# MCU.net
KiCad netlist of a schematic drawn in Altium Designer
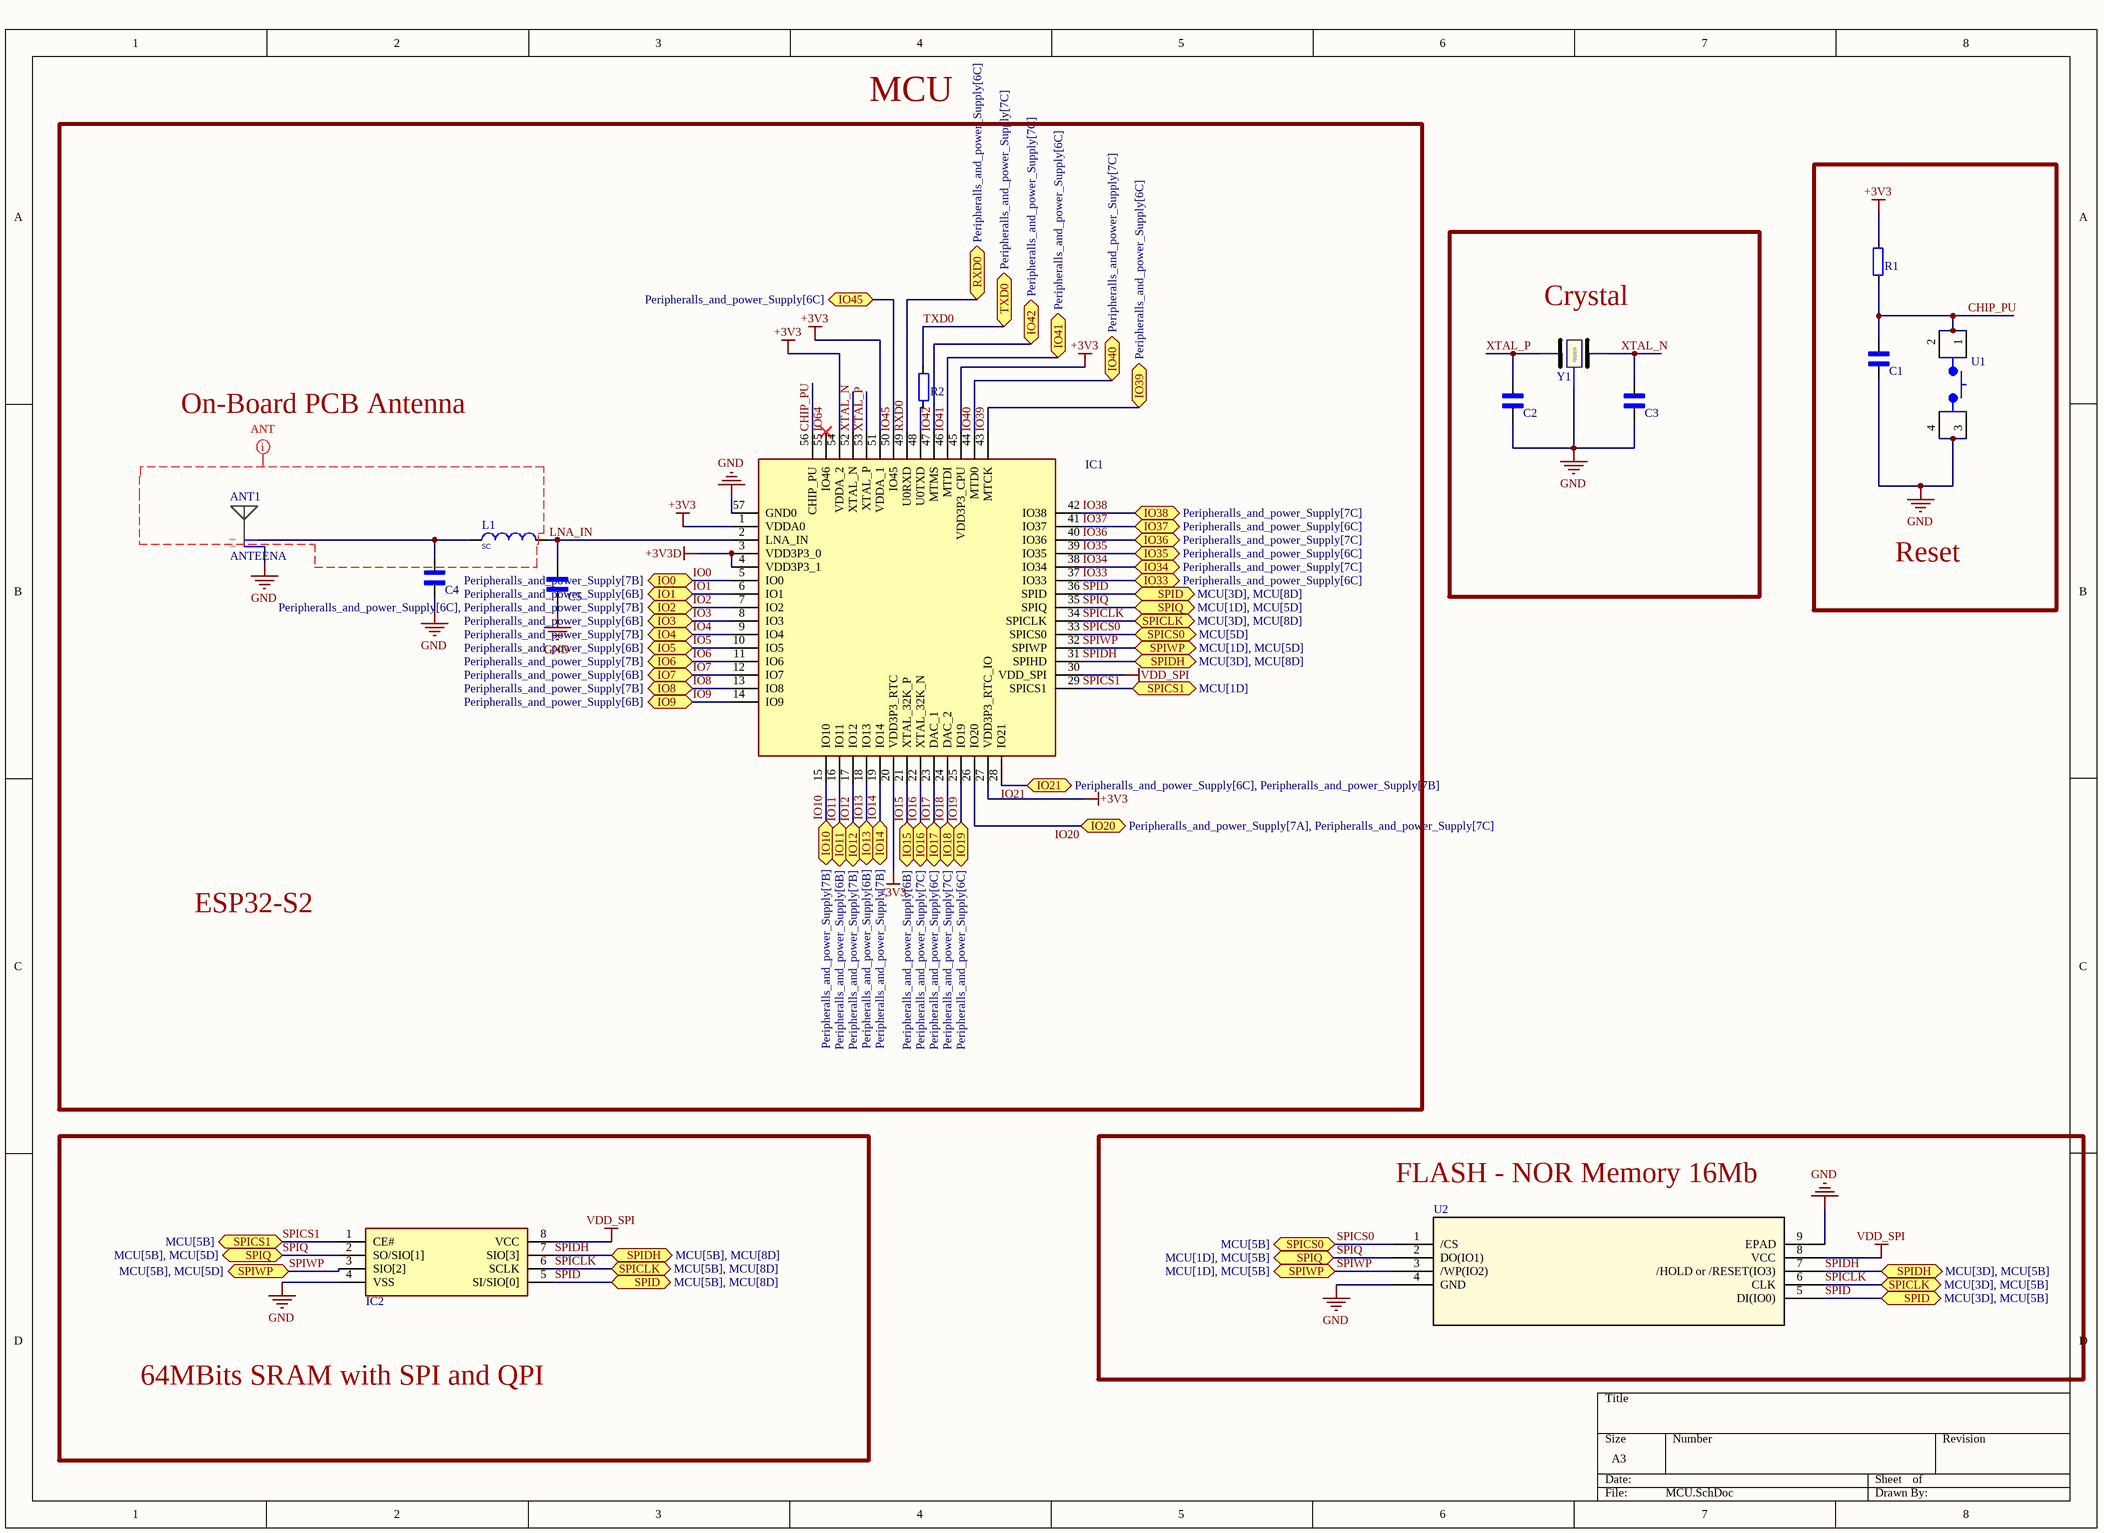
[diagram p0: MCU.SchDoc]

(export (version "E")
  (design (tool "Eeschema 10.0.6"))
  (components
    (comp (ref "ANT1")
      (value "ANTEENA")
      (footprint "Antenna_2.4GHz")
      (libsource (lib "ESP32-S2") (part "ANTEENA"))
    )
    (comp (ref "C1") (value "CAP_0603") (footprint "CAP_0603") (libsource (lib "") (part "CAP_0603_1")))
    (comp (ref "C2") (value "CAP_0603") (footprint "CAP_0603") (libsource (lib "ESP32-S2") (part "CAP_0603")))
    (comp (ref "C3") (value "CAP_0603") (footprint "CAP_0603") (libsource (lib "ESP32-S2") (part "CAP_0603")))
    (comp (ref "C4") (value "CAP_0603") (footprint "CAP_0603") (libsource (lib "ESP32-S2") (part "CAP_0603")))
    (comp (ref "C5") (value "CAP_0603") (footprint "CAP_0603") (libsource (lib "ESP32-S2") (part "CAP_0603")))
    (comp (ref "IC1")
      (value "ESP32-S2")
      (footprint "QFN-56")
      (description "SMD WI-FI IC, ESP32-S2, SINGAL-C")
      (fields (field (name "MF") "Espressif Systems"))
      (libsource (lib "ESP32-S2") (part "ESP32-S2"))
    )
    (comp (ref "IC2")
      (value "PSRAM")
      (footprint "SOIC8 _PSRAM")
      (description "SOP-8_150mil  SRAM ROHS")
      (fields (field (name "MANUFACTURER_PART_NUMBER") "LY68L6400SLIT"))
      (libsource (lib "ESP32-S2") (part "LY68L6400SLIT"))
    )
    (comp (ref "L1")
      (value "SC")
      (footprint "IND_0402")
      (description "Inductor RF Chip Multi-Layer 2nH 0.3nH 100MHz 8Q-Factor Air 900mA 90mOhm DCR 0402 Automotive T/R")
      (fields (field (name "MP") "LQG15HZ2N0S02D") (field (name "Comment") "IND_0402"))
      (libsource (lib "ESP32-S2") (part "IND_2.0nH_0402"))
    )
    (comp (ref "R1") (value "RES_0603") (footprint "RES_0603") (libsource (lib "ESP32-S2") (part "RES_0603")))
    (comp (ref "R2") (value "RES_0603") (footprint "RES_0603") (libsource (lib "ESP32-S2") (part "RES_0603")))
    (comp (ref "U1")
      (value "TACT SWITCH")
      (footprint "SW_TL3305AF260QG")
      (description "Tactile Switch SPST-NO Top Actuated Surface Mount")
      (fields (field (name "MF") "E-Switch") (field (name "MP") "TL3305AF260QG"))
      (libsource (lib "ESP32-S2") (part "TL3305AF260QG"))
    )
    (comp (ref "U2")
      (value "NOR FLASH IC")
      (footprint "FLASH USON2x3x0.6mm")
      (description "FLASH - NOR Memory IC 16Mb (2M x 8) SPI - Quad I/O 133 MHz 6 ns 8-USON (2x3)")
      (fields
        (field (name "MANUFACTURER_PART_NUMBER") "W25Q16JVUXIQ")
        (field (name "COPYRIGHT") "Copyright (C) 2022 Ultra Librarian. All rights reserved.")
      )
      (libsource (lib "ESP32-S2") (part "W25Q16JVUXIQ"))
    )
    (comp (ref "Y1")
      (value "CRYSTAL")
      (footprint "3225_CRYSTA_4P")
      (description "CRYSTAL_40MhZ_10ppm_15pF")
      (libsource (lib "ESP32-S2") (part "CRYSTAL_40MhZ_10ppm_15pF"))
    )
  )
  (nets
    (net (code "1") (name "+3V3") (class "Default")
      (node (ref "IC1") (pin "1") (pinfunction "VDDA0_1") (pintype "passive"))
      (node (ref "IC1") (pin "20") (pinfunction "VDD3P3_RTC_20") (pintype "passive"))
      (node (ref "IC1") (pin "27") (pinfunction "VDD3P3_RTC_IO_27") (pintype "passive"))
      (node (ref "IC1") (pin "45") (pinfunction "VDD3P3_CPU_45") (pintype "passive"))
      (node (ref "IC1") (pin "51") (pinfunction "VDDA_1_51") (pintype "passive"))
      (node (ref "IC1") (pin "54") (pinfunction "VDDA_2_54") (pintype "passive"))
      (node (ref "R1") (pin "1") (pinfunction "1_1") (pintype "passive"))
    )
    (net (code "2") (name "+3V3D") (class "Default")
      (node (ref "IC1") (pin "3") (pinfunction "VDD3P3_0_3") (pintype "passive"))
      (node (ref "IC1") (pin "4") (pinfunction "VDD3P3_1_4") (pintype "passive"))
    )
    (net (code "3") (name "/CHIP_PU") (class "Default")
      (node (ref "C1") (pin "1") (pinfunction "1_1") (pintype "passive"))
      (node (ref "IC1") (pin "56") (pinfunction "CHIP_PU_56") (pintype "passive"))
      (node (ref "R1") (pin "2") (pinfunction "2_2") (pintype "passive"))
      (node (ref "U1") (pin "1") (pinfunction "1_1") (pintype "passive"))
      (node (ref "U1") (pin "2") (pinfunction "2_2") (pintype "passive"))
    )
    (net (code "4") (name "/IO0") (class "Default")
      (node (ref "IC1") (pin "5") (pinfunction "IO0_5") (pintype "passive"))
    )
    (net (code "5") (name "/IO1") (class "Default")
      (node (ref "IC1") (pin "6") (pinfunction "IO1_6") (pintype "passive"))
    )
    (net (code "6") (name "/IO2") (class "Default")
      (node (ref "IC1") (pin "7") (pinfunction "IO2_7") (pintype "passive"))
    )
    (net (code "7") (name "/IO3") (class "Default")
      (node (ref "IC1") (pin "8") (pinfunction "IO3_8") (pintype "passive"))
    )
    (net (code "8") (name "/IO4") (class "Default")
      (node (ref "IC1") (pin "9") (pinfunction "IO4_9") (pintype "passive"))
    )
    (net (code "9") (name "/IO5") (class "Default")
      (node (ref "IC1") (pin "10") (pinfunction "IO5_10") (pintype "passive"))
    )
    (net (code "10") (name "/IO6") (class "Default")
      (node (ref "IC1") (pin "11") (pinfunction "IO6_11") (pintype "passive"))
    )
    (net (code "11") (name "/IO7") (class "Default")
      (node (ref "IC1") (pin "12") (pinfunction "IO7_12") (pintype "passive"))
    )
    (net (code "12") (name "/IO8") (class "Default")
      (node (ref "IC1") (pin "13") (pinfunction "IO8_13") (pintype "passive"))
    )
    (net (code "13") (name "/IO9") (class "Default")
      (node (ref "IC1") (pin "14") (pinfunction "IO9_14") (pintype "passive"))
    )
    (net (code "14") (name "/IO10") (class "Default")
      (node (ref "IC1") (pin "15") (pinfunction "IO10_15") (pintype "passive"))
    )
    (net (code "15") (name "/IO11") (class "Default")
      (node (ref "IC1") (pin "16") (pinfunction "IO11_16") (pintype "passive"))
    )
    (net (code "16") (name "/IO12") (class "Default")
      (node (ref "IC1") (pin "17") (pinfunction "IO12_17") (pintype "passive"))
    )
    (net (code "17") (name "/IO13") (class "Default")
      (node (ref "IC1") (pin "18") (pinfunction "IO13_18") (pintype "passive"))
    )
    (net (code "18") (name "/IO14") (class "Default")
      (node (ref "IC1") (pin "19") (pinfunction "IO14_19") (pintype "passive"))
    )
    (net (code "19") (name "/IO15") (class "Default")
      (node (ref "IC1") (pin "21") (pinfunction "XTAL_32K_P_21") (pintype "passive"))
    )
    (net (code "20") (name "/IO16") (class "Default")
      (node (ref "IC1") (pin "22") (pinfunction "XTAL_32K_N_22") (pintype "passive"))
    )
    (net (code "21") (name "/IO17") (class "Default")
      (node (ref "IC1") (pin "23") (pinfunction "DAC_1_23") (pintype "passive"))
    )
    (net (code "22") (name "/IO18") (class "Default")
      (node (ref "IC1") (pin "24") (pinfunction "DAC_2_24") (pintype "passive"))
    )
    (net (code "23") (name "/IO19") (class "Default")
      (node (ref "IC1") (pin "25") (pinfunction "IO19_25") (pintype "passive"))
    )
    (net (code "24") (name "/IO20") (class "Default")
      (node (ref "IC1") (pin "26") (pinfunction "IO20_26") (pintype "passive"))
    )
    (net (code "25") (name "/IO21") (class "Default")
      (node (ref "IC1") (pin "28") (pinfunction "IO21_28") (pintype "passive"))
    )
    (net (code "26") (name "/IO33") (class "Default")
      (node (ref "IC1") (pin "37") (pinfunction "IO33_37") (pintype "passive"))
    )
    (net (code "27") (name "/IO34") (class "Default")
      (node (ref "IC1") (pin "38") (pinfunction "IO34_38") (pintype "passive"))
    )
    (net (code "28") (name "/IO35") (class "Default")
      (node (ref "IC1") (pin "39") (pinfunction "IO35_39") (pintype "passive"))
    )
    (net (code "29") (name "/IO36") (class "Default")
      (node (ref "IC1") (pin "40") (pinfunction "IO36_40") (pintype "passive"))
    )
    (net (code "30") (name "/IO37") (class "Default")
      (node (ref "IC1") (pin "41") (pinfunction "IO37_41") (pintype "passive"))
    )
    (net (code "31") (name "/IO38") (class "Default")
      (node (ref "IC1") (pin "42") (pinfunction "IO38_42") (pintype "passive"))
    )
    (net (code "32") (name "/IO39") (class "Default")
      (node (ref "IC1") (pin "43") (pinfunction "MTCK_43") (pintype "passive"))
    )
    (net (code "33") (name "/IO40") (class "Default")
      (node (ref "IC1") (pin "44") (pinfunction "MTD0_44") (pintype "passive"))
    )
    (net (code "34") (name "/IO41") (class "Default")
      (node (ref "IC1") (pin "46") (pinfunction "MTDI_46") (pintype "passive"))
    )
    (net (code "35") (name "/IO42") (class "Default")
      (node (ref "IC1") (pin "47") (pinfunction "MTMS_47") (pintype "passive"))
    )
    (net (code "36") (name "/IO45") (class "Default")
      (node (ref "IC1") (pin "50") (pinfunction "IO45_50") (pintype "passive"))
    )
    (net (code "37") (name "/IO64") (class "Default")
      (node (ref "IC1") (pin "55") (pinfunction "IO46_55") (pintype "passive+no_connect"))
    )
    (net (code "38") (name "/LNA_IN") (class "Default")
      (node (ref "C5") (pin "2") (pinfunction "2_2") (pintype "passive"))
      (node (ref "IC1") (pin "2") (pinfunction "LNA_IN_2") (pintype "passive"))
      (node (ref "L1") (pin "2") (pinfunction "2_2") (pintype "passive"))
    )
    (net (code "39") (name "/RXD0") (class "Default")
      (node (ref "IC1") (pin "49") (pinfunction "U0RXD_49") (pintype "passive"))
    )
    (net (code "40") (name "/SPICLK") (class "Default")
      (node (ref "IC1") (pin "34") (pinfunction "SPICLK_34") (pintype "passive"))
      (node (ref "IC2") (pin "6") (pinfunction "SCLK_6") (pintype "passive"))
      (node (ref "U2") (pin "6") (pinfunction "CLK_6") (pintype "passive"))
    )
    (net (code "41") (name "/SPICS0") (class "Default")
      (node (ref "IC1") (pin "33") (pinfunction "SPICS0_33") (pintype "passive"))
      (node (ref "U2") (pin "1") (pinfunction "/CS_1") (pintype "passive"))
    )
    (net (code "42") (name "/SPICS1") (class "Default")
      (node (ref "IC1") (pin "29") (pinfunction "SPICS1_29") (pintype "passive"))
      (node (ref "IC2") (pin "1") (pinfunction "CE#_1") (pintype "passive"))
    )
    (net (code "43") (name "/SPID") (class "Default")
      (node (ref "IC1") (pin "36") (pinfunction "SPID_36") (pintype "passive"))
      (node (ref "IC2") (pin "5") (pinfunction "SI/SIO[0]_5") (pintype "passive"))
      (node (ref "U2") (pin "5") (pinfunction "DI(IO0)_5") (pintype "passive"))
    )
    (net (code "44") (name "/SPIDH") (class "Default")
      (node (ref "IC1") (pin "31") (pinfunction "SPIHD_31") (pintype "passive"))
      (node (ref "IC2") (pin "7") (pinfunction "SIO[3]_7") (pintype "passive"))
      (node (ref "U2") (pin "7") (pinfunction "/HOLD_or_/RESET(IO3)_7") (pintype "passive"))
    )
    (net (code "45") (name "/SPIQ") (class "Default")
      (node (ref "IC1") (pin "35") (pinfunction "SPIQ_35") (pintype "passive"))
      (node (ref "IC2") (pin "2") (pinfunction "SO/SIO[1]_2") (pintype "passive"))
      (node (ref "U2") (pin "2") (pinfunction "DO(IO1)_2") (pintype "passive"))
    )
    (net (code "46") (name "/SPIWP") (class "Default")
      (node (ref "IC1") (pin "32") (pinfunction "SPIWP_32") (pintype "passive"))
      (node (ref "IC2") (pin "3") (pinfunction "SIO[2]_3") (pintype "passive"))
      (node (ref "U2") (pin "3") (pinfunction "/WP(IO2)_3") (pintype "passive"))
    )
    (net (code "47") (name "/TXD0") (class "Default")
      (node (ref "R2") (pin "2") (pinfunction "2_2") (pintype "passive"))
    )
    (net (code "48") (name "/XTAL_N") (class "Default")
      (node (ref "C3") (pin "2") (pinfunction "2_2") (pintype "passive"))
      (node (ref "IC1") (pin "52") (pinfunction "XTAL_N_52") (pintype "passive"))
      (node (ref "Y1") (pin "1") (pinfunction "1_1") (pintype "passive"))
    )
    (net (code "49") (name "/XTAL_P") (class "Default")
      (node (ref "C2") (pin "2") (pinfunction "2_2") (pintype "passive"))
      (node (ref "IC1") (pin "53") (pinfunction "XTAL_P_53") (pintype "passive"))
      (node (ref "Y1") (pin "3") (pinfunction "3_3") (pintype "passive"))
    )
    (net (code "50") (name "GND") (class "Default")
      (node (ref "ANT1") (pin "1") (pinfunction "GND_1") (pintype "passive"))
      (node (ref "C1") (pin "2") (pinfunction "2_2") (pintype "passive"))
      (node (ref "C2") (pin "1") (pinfunction "1_1") (pintype "passive"))
      (node (ref "C3") (pin "1") (pinfunction "1_1") (pintype "passive"))
      (node (ref "C4") (pin "1") (pinfunction "1_1") (pintype "passive"))
      (node (ref "C5") (pin "1") (pinfunction "1_1") (pintype "passive"))
      (node (ref "IC1") (pin "57") (pinfunction "GND0_57") (pintype "passive"))
      (node (ref "IC2") (pin "4") (pinfunction "VSS_4") (pintype "passive"))
      (node (ref "U1") (pin "3") (pinfunction "3_3") (pintype "passive"))
      (node (ref "U1") (pin "4") (pinfunction "4_4") (pintype "passive"))
      (node (ref "U2") (pin "4") (pinfunction "GND_4") (pintype "passive"))
      (node (ref "U2") (pin "9") (pinfunction "EPAD_9") (pintype "passive"))
      (node (ref "Y1") (pin "2") (pinfunction "2_2") (pintype "passive"))
    )
    (net (code "51") (name "Net-(ANT1-FEED)") (class "Default")
      (node (ref "ANT1") (pin "2") (pinfunction "FEED_2") (pintype "passive"))
      (node (ref "C4") (pin "2") (pinfunction "2_2") (pintype "passive"))
      (node (ref "L1") (pin "1") (pinfunction "1_1") (pintype "passive"))
    )
    (net (code "52") (name "Net-(IC1-U0TXD)") (class "Default")
      (node (ref "IC1") (pin "48") (pinfunction "U0TXD_48") (pintype "passive"))
      (node (ref "R2") (pin "1") (pinfunction "1_1") (pintype "passive"))
    )
    (net (code "53") (name "VDD_SPI") (class "Default")
      (node (ref "IC1") (pin "30") (pinfunction "VDD_SPI_30") (pintype "passive"))
      (node (ref "IC2") (pin "8") (pinfunction "VCC_8") (pintype "passive"))
      (node (ref "U2") (pin "8") (pinfunction "VCC_8") (pintype "passive"))
    )
  )
)
